# MCU.net
KiCad netlist of a schematic drawn in Altium Designer
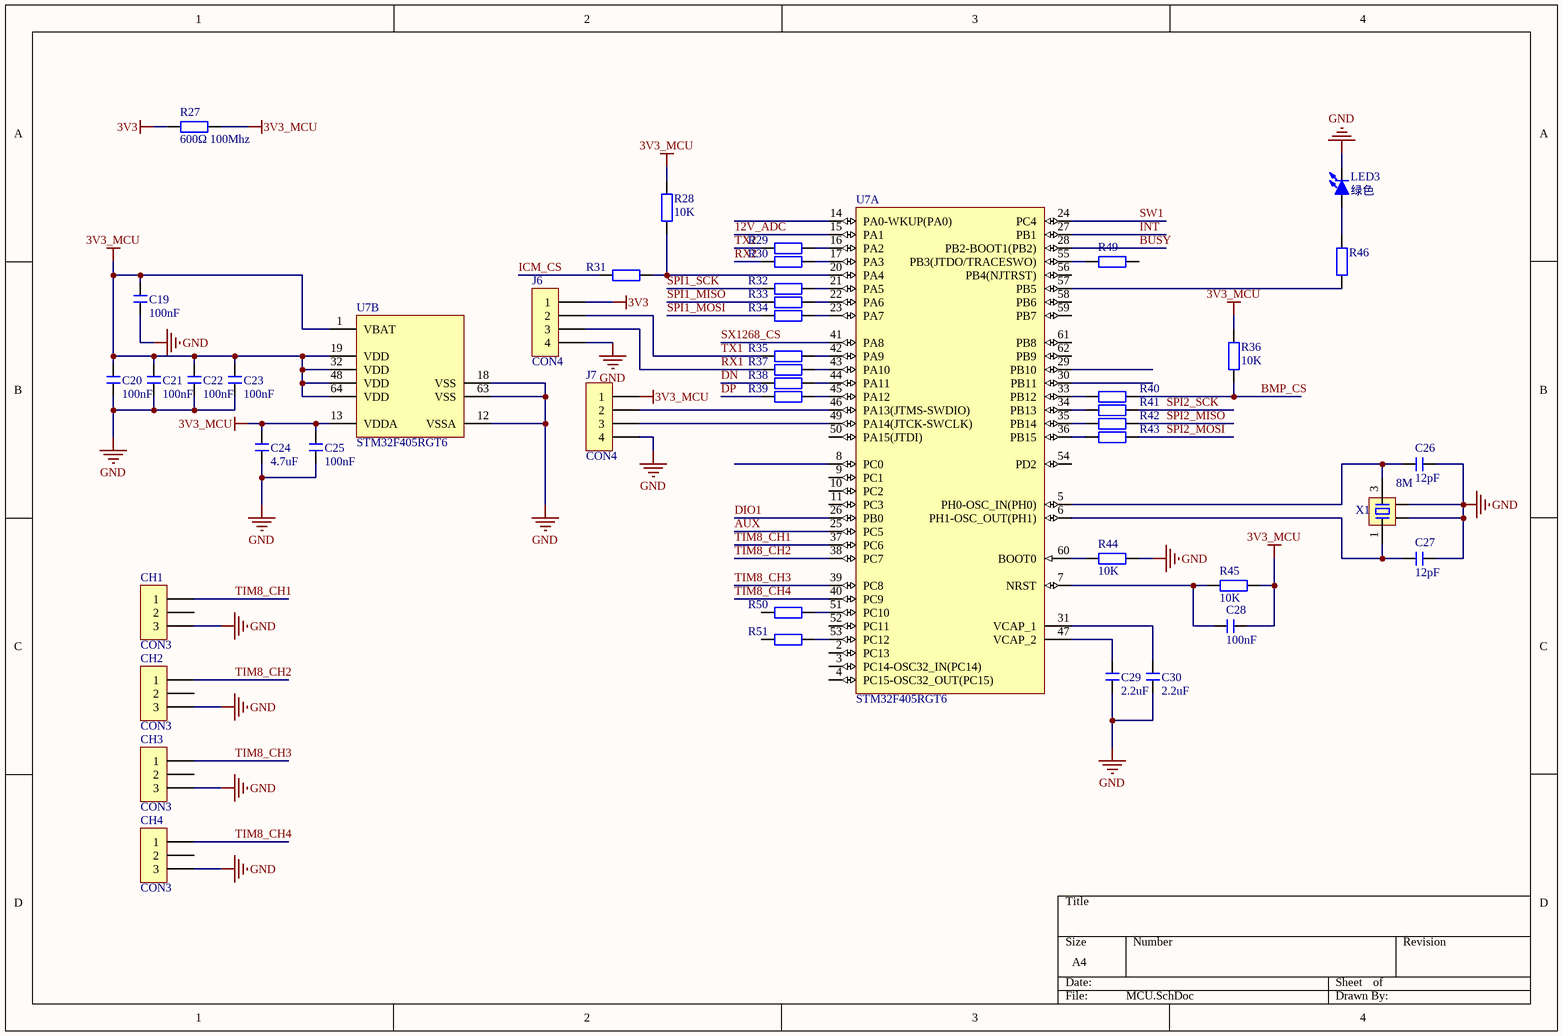
[diagram p0: MCU.SchDoc]

(export (version "E")
  (design (tool "Eeschema 10.0.6"))
  (components
    (comp (ref "C19")
      (value "100nF")
      (footprint "C 0603_L")
      (description "无极性贴片电容")
      (fields (field (name "版权归属") "源创客"))
      (libsource (lib "3.1   - 电阻-电容-电感") (part "C"))
    )
    (comp (ref "C20")
      (value "100nF")
      (footprint "C 0603_L")
      (description "无极性贴片电容")
      (fields (field (name "版权归属") "源创客"))
      (libsource (lib "3.1   - 电阻-电容-电感") (part "C"))
    )
    (comp (ref "C21")
      (value "100nF")
      (footprint "C 0603_L")
      (description "无极性贴片电容")
      (fields (field (name "版权归属") "源创客"))
      (libsource (lib "3.1   - 电阻-电容-电感") (part "C"))
    )
    (comp (ref "C22")
      (value "100nF")
      (footprint "C 0603_L")
      (description "无极性贴片电容")
      (fields (field (name "版权归属") "源创客"))
      (libsource (lib "3.1   - 电阻-电容-电感") (part "C"))
    )
    (comp (ref "C23")
      (value "100nF")
      (footprint "C 0603_L")
      (description "无极性贴片电容")
      (fields (field (name "版权归属") "源创客"))
      (libsource (lib "3.1   - 电阻-电容-电感") (part "C"))
    )
    (comp (ref "C24")
      (value "4.7uF")
      (footprint "C 0603_L")
      (description "无极性贴片电容")
      (fields (field (name "版权归属") "源创客"))
      (libsource (lib "3.1   - 电阻-电容-电感") (part "C"))
    )
    (comp (ref "C25")
      (value "100nF")
      (footprint "C 0603_L")
      (description "无极性贴片电容")
      (fields (field (name "版权归属") "源创客"))
      (libsource (lib "3.1   - 电阻-电容-电感") (part "C"))
    )
    (comp (ref "C26")
      (value "12pF")
      (footprint "C 0603_L")
      (description "无极性贴片电容")
      (fields (field (name "版权归属") "源创客"))
      (libsource (lib "3.1   - 电阻-电容-电感") (part "C"))
    )
    (comp (ref "C27")
      (value "12pF")
      (footprint "C 0603_L")
      (description "无极性贴片电容")
      (fields (field (name "版权归属") "源创客"))
      (libsource (lib "3.1   - 电阻-电容-电感") (part "C"))
    )
    (comp (ref "C28")
      (value "100nF")
      (footprint "C 0603_L")
      (description "无极性贴片电容")
      (fields (field (name "版权归属") "源创客"))
      (libsource (lib "3.1   - 电阻-电容-电感") (part "C"))
    )
    (comp (ref "C29")
      (value "2.2uF")
      (footprint "C 0603_L")
      (description "无极性贴片电容")
      (fields (field (name "版权归属") "源创客"))
      (libsource (lib "3.1   - 电阻-电容-电感") (part "C"))
    )
    (comp (ref "C30")
      (value "2.2uF")
      (footprint "C 0603_L")
      (description "无极性贴片电容")
      (fields (field (name "版权归属") "源创客"))
      (libsource (lib "3.1   - 电阻-电容-电感") (part "C"))
    )
    (comp (ref "CH1")
      (value "CON3")
      (footprint "HDR2.54-LI-3P")
      (description "Connector")
      (libsource (lib "插件") (part "CON3"))
    )
    (comp (ref "CH2")
      (value "CON3")
      (footprint "HDR2.54-LI-3P")
      (description "Connector")
      (libsource (lib "插件") (part "CON3"))
    )
    (comp (ref "CH3")
      (value "CON3")
      (footprint "HDR2.54-LI-3P")
      (description "Connector")
      (libsource (lib "插件") (part "CON3"))
    )
    (comp (ref "CH4")
      (value "CON3")
      (footprint "HDR2.54-LI-3P")
      (description "Connector")
      (libsource (lib "插件") (part "CON3"))
    )
    (comp (ref "J6")
      (value "CON4")
      (footprint "HDR2.54-LI-4P")
      (description "Connector")
      (libsource (lib "插件") (part "CON4"))
    )
    (comp (ref "J7")
      (value "CON4")
      (footprint "HDR2.54-LI-4P")
      (description "Connector")
      (libsource (lib "插件") (part "CON4"))
    )
    (comp (ref "LED3")
      (value "绿色")
      (footprint "LED 0805G")
      (description "贴片LED")
      (fields (field (name "版权归属") "源创客"))
      (libsource (lib "9.1   - LED") (part "LED-SMD"))
    )
    (comp (ref "R27")
      (value "600Ω 100Mhz")
      (footprint "R 0805_L")
      (description "磁珠")
      (fields (field (name "版权归属") "源创客"))
      (libsource (lib "3.1   - 电阻-电容-电感") (part "R"))
    )
    (comp (ref "R28")
      (value "10K")
      (footprint "R 0603_L")
      (description "贴片电阻")
      (fields (field (name "版权归属") "源创客"))
      (libsource (lib "3.1   - 电阻-电容-电感") (part "R"))
    )
    (comp (ref "R29")
      (value "~")
      (footprint "R 0603_L")
      (description "贴片电阻")
      (fields (field (name "版权归属") "源创客"))
      (libsource (lib "3.1   - 电阻-电容-电感") (part "R"))
    )
    (comp (ref "R30")
      (value "~")
      (footprint "R 0603_L")
      (description "贴片电阻")
      (fields (field (name "版权归属") "源创客"))
      (libsource (lib "3.1   - 电阻-电容-电感") (part "R"))
    )
    (comp (ref "R31")
      (value "~")
      (footprint "R 0603_L")
      (description "贴片电阻")
      (fields (field (name "版权归属") "源创客"))
      (libsource (lib "3.1   - 电阻-电容-电感") (part "R"))
    )
    (comp (ref "R32")
      (value "~")
      (footprint "R 0603_L")
      (description "贴片电阻")
      (fields (field (name "版权归属") "源创客"))
      (libsource (lib "3.1   - 电阻-电容-电感") (part "R"))
    )
    (comp (ref "R33")
      (value "~")
      (footprint "R 0603_L")
      (description "贴片电阻")
      (fields (field (name "版权归属") "源创客"))
      (libsource (lib "3.1   - 电阻-电容-电感") (part "R"))
    )
    (comp (ref "R34")
      (value "~")
      (footprint "R 0603_L")
      (description "贴片电阻")
      (fields (field (name "版权归属") "源创客"))
      (libsource (lib "3.1   - 电阻-电容-电感") (part "R"))
    )
    (comp (ref "R35")
      (value "~")
      (footprint "R 0603_L")
      (description "贴片电阻")
      (fields (field (name "版权归属") "源创客"))
      (libsource (lib "3.1   - 电阻-电容-电感") (part "R"))
    )
    (comp (ref "R36")
      (value "10K")
      (footprint "R 0603_L")
      (description "贴片电阻")
      (fields (field (name "版权归属") "源创客"))
      (libsource (lib "3.1   - 电阻-电容-电感") (part "R"))
    )
    (comp (ref "R37")
      (value "~")
      (footprint "R 0603_L")
      (description "贴片电阻")
      (fields (field (name "版权归属") "源创客"))
      (libsource (lib "3.1   - 电阻-电容-电感") (part "R"))
    )
    (comp (ref "R38")
      (value "~")
      (footprint "R 0603_L")
      (description "贴片电阻")
      (fields (field (name "版权归属") "源创客"))
      (libsource (lib "3.1   - 电阻-电容-电感") (part "R"))
    )
    (comp (ref "R39")
      (value "~")
      (footprint "R 0603_L")
      (description "贴片电阻")
      (fields (field (name "版权归属") "源创客"))
      (libsource (lib "3.1   - 电阻-电容-电感") (part "R"))
    )
    (comp (ref "R40")
      (value "~")
      (footprint "R 0603_L")
      (description "贴片电阻")
      (fields (field (name "版权归属") "源创客"))
      (libsource (lib "3.1   - 电阻-电容-电感") (part "R"))
    )
    (comp (ref "R41")
      (value "~")
      (footprint "R 0603_L")
      (description "贴片电阻")
      (fields (field (name "版权归属") "源创客"))
      (libsource (lib "3.1   - 电阻-电容-电感") (part "R"))
    )
    (comp (ref "R42")
      (value "~")
      (footprint "R 0603_L")
      (description "贴片电阻")
      (fields (field (name "版权归属") "源创客"))
      (libsource (lib "3.1   - 电阻-电容-电感") (part "R"))
    )
    (comp (ref "R43")
      (value "~")
      (footprint "R 0603_L")
      (description "贴片电阻")
      (fields (field (name "版权归属") "源创客"))
      (libsource (lib "3.1   - 电阻-电容-电感") (part "R"))
    )
    (comp (ref "R44")
      (value "10K")
      (footprint "R 0603_L")
      (description "贴片电阻")
      (fields (field (name "版权归属") "源创客"))
      (libsource (lib "3.1   - 电阻-电容-电感") (part "R"))
    )
    (comp (ref "R45")
      (value "10K")
      (footprint "R 0603_L")
      (description "贴片电阻")
      (fields (field (name "版权归属") "源创客"))
      (libsource (lib "3.1   - 电阻-电容-电感") (part "R"))
    )
    (comp (ref "R46")
      (value "~")
      (footprint "R 0603_L")
      (description "贴片电阻")
      (fields (field (name "版权归属") "源创客"))
      (libsource (lib "3.1   - 电阻-电容-电感") (part "R"))
    )
    (comp (ref "R49")
      (value "~")
      (footprint "R 0603_L")
      (description "贴片电阻")
      (fields (field (name "版权归属") "源创客"))
      (libsource (lib "3.1   - 电阻-电容-电感") (part "R"))
    )
    (comp (ref "R50")
      (value "~")
      (footprint "R 0603_L")
      (description "贴片电阻")
      (fields (field (name "版权归属") "源创客"))
      (libsource (lib "3.1   - 电阻-电容-电感") (part "R"))
    )
    (comp (ref "R51")
      (value "~")
      (footprint "R 0603_L")
      (description "贴片电阻")
      (fields (field (name "版权归属") "源创客"))
      (libsource (lib "3.1   - 电阻-电容-电感") (part "R"))
    )
    (comp (ref "U7")
      (value "STM32F405RGT6")
      (footprint "STM-LQFP64_N")
      (fields (field (name "MANUFACTURER") "STMicroelectronics"))
      (libsource (lib "") (part "STM32F405RGT6_1"))
    )
    (comp (ref "X1")
      (value "8M")
      (footprint "OSC 3225-4P")
      (fields (field (name "版权归属") "源创客"))
      (libsource (lib "10.1 - 保险丝-晶振") (part "XTAL-4P"))
    )
  )
  (nets
    (net (code "1") (name "/12V_ADC") (class "Default")
      (node (ref "U7") (pin "15") (pinfunction "PA1_15") (pintype "bidirectional"))
    )
    (net (code "2") (name "/AUX") (class "Default")
      (node (ref "U7") (pin "25") (pinfunction "PC5_25") (pintype "bidirectional"))
    )
    (net (code "3") (name "/BMP_CS") (class "Default")
      (node (ref "R36") (pin "1") (pinfunction "1_1") (pintype "passive"))
      (node (ref "R40") (pin "2") (pinfunction "2_2") (pintype "passive"))
    )
    (net (code "4") (name "/BUSY") (class "Default")
      (node (ref "U7") (pin "28") (pinfunction "PB2-BOOT1(PB2)_28") (pintype "bidirectional"))
    )
    (net (code "5") (name "/DIO1") (class "Default")
      (node (ref "U7") (pin "26") (pinfunction "PB0_26") (pintype "bidirectional"))
    )
    (net (code "6") (name "/DN") (class "Default")
      (node (ref "R38") (pin "2") (pinfunction "2_2") (pintype "passive"))
    )
    (net (code "7") (name "/DP") (class "Default")
      (node (ref "R39") (pin "2") (pinfunction "2_2") (pintype "passive"))
    )
    (net (code "8") (name "/ICM_CS") (class "Default")
      (node (ref "R31") (pin "2") (pinfunction "2_2") (pintype "passive"))
    )
    (net (code "9") (name "/INT") (class "Default")
      (node (ref "U7") (pin "27") (pinfunction "PB1_27") (pintype "bidirectional"))
    )
    (net (code "10") (name "/RX1") (class "Default")
      (node (ref "J6") (pin "3") (pinfunction "3_3") (pintype "passive"))
      (node (ref "R37") (pin "2") (pinfunction "2_2") (pintype "passive"))
    )
    (net (code "11") (name "/RX2") (class "Default")
      (node (ref "R30") (pin "2") (pinfunction "2_2") (pintype "passive"))
    )
    (net (code "12") (name "/SPI1_MISO") (class "Default")
      (node (ref "R33") (pin "2") (pinfunction "2_2") (pintype "passive"))
    )
    (net (code "13") (name "/SPI1_MOSI") (class "Default")
      (node (ref "R34") (pin "2") (pinfunction "2_2") (pintype "passive"))
    )
    (net (code "14") (name "/SPI1_SCK") (class "Default")
      (node (ref "R32") (pin "2") (pinfunction "2_2") (pintype "passive"))
    )
    (net (code "15") (name "/SPI2_MISO") (class "Default")
      (node (ref "R42") (pin "2") (pinfunction "2_2") (pintype "passive"))
    )
    (net (code "16") (name "/SPI2_MOSI") (class "Default")
      (node (ref "R43") (pin "2") (pinfunction "2_2") (pintype "passive"))
    )
    (net (code "17") (name "/SPI2_SCK") (class "Default")
      (node (ref "R41") (pin "2") (pinfunction "2_2") (pintype "passive"))
    )
    (net (code "18") (name "/SW1") (class "Default")
      (node (ref "U7") (pin "24") (pinfunction "PC4_24") (pintype "bidirectional"))
    )
    (net (code "19") (name "/SX1268_CS") (class "Default")
      (node (ref "U7") (pin "41") (pinfunction "PA8_41") (pintype "bidirectional"))
    )
    (net (code "20") (name "/TIM8_CH1") (class "Default")
      (node (ref "CH1") (pin "1") (pinfunction "1_1") (pintype "passive"))
      (node (ref "U7") (pin "37") (pinfunction "PC6_37") (pintype "bidirectional"))
    )
    (net (code "21") (name "/TIM8_CH2") (class "Default")
      (node (ref "CH2") (pin "1") (pinfunction "1_1") (pintype "passive"))
      (node (ref "U7") (pin "38") (pinfunction "PC7_38") (pintype "bidirectional"))
    )
    (net (code "22") (name "/TIM8_CH3") (class "Default")
      (node (ref "CH3") (pin "1") (pinfunction "1_1") (pintype "passive"))
      (node (ref "U7") (pin "39") (pinfunction "PC8_39") (pintype "bidirectional"))
    )
    (net (code "23") (name "/TIM8_CH4") (class "Default")
      (node (ref "CH4") (pin "1") (pinfunction "1_1") (pintype "passive"))
      (node (ref "U7") (pin "40") (pinfunction "PC9_40") (pintype "bidirectional"))
    )
    (net (code "24") (name "/TX1") (class "Default")
      (node (ref "J6") (pin "2") (pinfunction "2_2") (pintype "passive"))
      (node (ref "R35") (pin "2") (pinfunction "2_2") (pintype "passive"))
    )
    (net (code "25") (name "/TX2") (class "Default")
      (node (ref "R29") (pin "2") (pinfunction "2_2") (pintype "passive"))
    )
    (net (code "26") (name "3V3") (class "Default")
      (node (ref "J6") (pin "1") (pinfunction "1_1") (pintype "passive"))
      (node (ref "R27") (pin "1") (pinfunction "1_1") (pintype "passive"))
    )
    (net (code "27") (name "3V3_MCU") (class "Default")
      (node (ref "C19") (pin "2") (pinfunction "2_2") (pintype "passive"))
      (node (ref "C20") (pin "2") (pinfunction "2_2") (pintype "passive"))
      (node (ref "C21") (pin "2") (pinfunction "2_2") (pintype "passive"))
      (node (ref "C22") (pin "2") (pinfunction "2_2") (pintype "passive"))
      (node (ref "C23") (pin "2") (pinfunction "2_2") (pintype "passive"))
      (node (ref "C24") (pin "2") (pinfunction "2_2") (pintype "passive"))
      (node (ref "C25") (pin "2") (pinfunction "2_2") (pintype "passive"))
      (node (ref "C28") (pin "1") (pinfunction "1_1") (pintype "passive"))
      (node (ref "J7") (pin "1") (pinfunction "1_1") (pintype "passive"))
      (node (ref "R27") (pin "2") (pinfunction "2_2") (pintype "passive"))
      (node (ref "R28") (pin "2") (pinfunction "2_2") (pintype "passive"))
      (node (ref "R36") (pin "2") (pinfunction "2_2") (pintype "passive"))
      (node (ref "R45") (pin "2") (pinfunction "2_2") (pintype "passive"))
      (node (ref "U7") (pin "1") (pinfunction "VBAT_1") (pintype "power_in"))
      (node (ref "U7") (pin "13") (pinfunction "VDDA_13") (pintype "power_in"))
      (node (ref "U7") (pin "19") (pinfunction "VDD_19") (pintype "power_in"))
      (node (ref "U7") (pin "32") (pinfunction "VDD_32") (pintype "power_in"))
      (node (ref "U7") (pin "48") (pinfunction "VDD_48") (pintype "power_in"))
      (node (ref "U7") (pin "64") (pinfunction "VDD_64") (pintype "power_in"))
    )
    (net (code "28") (name "GND") (class "Default")
      (node (ref "C19") (pin "1") (pinfunction "1_1") (pintype "passive"))
      (node (ref "C20") (pin "1") (pinfunction "1_1") (pintype "passive"))
      (node (ref "C21") (pin "1") (pinfunction "1_1") (pintype "passive"))
      (node (ref "C22") (pin "1") (pinfunction "1_1") (pintype "passive"))
      (node (ref "C23") (pin "1") (pinfunction "1_1") (pintype "passive"))
      (node (ref "C24") (pin "1") (pinfunction "1_1") (pintype "passive"))
      (node (ref "C25") (pin "1") (pinfunction "1_1") (pintype "passive"))
      (node (ref "C26") (pin "1") (pinfunction "1_1") (pintype "passive"))
      (node (ref "C27") (pin "1") (pinfunction "1_1") (pintype "passive"))
      (node (ref "C29") (pin "1") (pinfunction "1_1") (pintype "passive"))
      (node (ref "C30") (pin "1") (pinfunction "1_1") (pintype "passive"))
      (node (ref "CH1") (pin "3") (pinfunction "3_3") (pintype "passive"))
      (node (ref "CH2") (pin "3") (pinfunction "3_3") (pintype "passive"))
      (node (ref "CH3") (pin "3") (pinfunction "3_3") (pintype "passive"))
      (node (ref "CH4") (pin "3") (pinfunction "3_3") (pintype "passive"))
      (node (ref "J6") (pin "4") (pinfunction "4_4") (pintype "passive"))
      (node (ref "J7") (pin "4") (pinfunction "4_4") (pintype "passive"))
      (node (ref "LED3") (pin "2") (pinfunction "K_2") (pintype "passive"))
      (node (ref "R44") (pin "2") (pinfunction "2_2") (pintype "passive"))
      (node (ref "U7") (pin "12") (pinfunction "VSSA_12") (pintype "power_in"))
      (node (ref "U7") (pin "18") (pinfunction "VSS_18") (pintype "power_in"))
      (node (ref "U7") (pin "63") (pinfunction "VSS_63") (pintype "power_in"))
      (node (ref "X1") (pin "2") (pinfunction "2_2") (pintype "passive"))
      (node (ref "X1") (pin "4") (pinfunction "4_4") (pintype "passive"))
    )
    (net (code "29") (name "Net-(LED3-A)") (class "Default")
      (node (ref "LED3") (pin "1") (pinfunction "A_1") (pintype "passive"))
      (node (ref "R46") (pin "2") (pinfunction "2_2") (pintype "passive"))
    )
    (net (code "30") (name "Net-(U7A-BOOT0)") (class "Default")
      (node (ref "R44") (pin "1") (pinfunction "1_1") (pintype "passive"))
      (node (ref "U7") (pin "60") (pinfunction "BOOT0_60") (pintype "input"))
    )
    (net (code "31") (name "Net-(U7A-NRST)") (class "Default")
      (node (ref "C28") (pin "2") (pinfunction "2_2") (pintype "passive"))
      (node (ref "R45") (pin "1") (pinfunction "1_1") (pintype "passive"))
      (node (ref "U7") (pin "7") (pinfunction "NRST_7") (pintype "bidirectional"))
    )
    (net (code "32") (name "Net-(U7A-PA2)") (class "Default")
      (node (ref "R29") (pin "1") (pinfunction "1_1") (pintype "passive"))
      (node (ref "U7") (pin "16") (pinfunction "PA2_16") (pintype "bidirectional"))
    )
    (net (code "33") (name "Net-(U7A-PA3)") (class "Default")
      (node (ref "R30") (pin "1") (pinfunction "1_1") (pintype "passive"))
      (node (ref "U7") (pin "17") (pinfunction "PA3_17") (pintype "bidirectional"))
    )
    (net (code "34") (name "Net-(U7A-PA4)") (class "Default")
      (node (ref "R28") (pin "1") (pinfunction "1_1") (pintype "passive"))
      (node (ref "R31") (pin "1") (pinfunction "1_1") (pintype "passive"))
      (node (ref "U7") (pin "20") (pinfunction "PA4_20") (pintype "bidirectional"))
    )
    (net (code "35") (name "Net-(U7A-PA5)") (class "Default")
      (node (ref "R32") (pin "1") (pinfunction "1_1") (pintype "passive"))
      (node (ref "U7") (pin "21") (pinfunction "PA5_21") (pintype "bidirectional"))
    )
    (net (code "36") (name "Net-(U7A-PA6)") (class "Default")
      (node (ref "R33") (pin "1") (pinfunction "1_1") (pintype "passive"))
      (node (ref "U7") (pin "22") (pinfunction "PA6_22") (pintype "bidirectional"))
    )
    (net (code "37") (name "Net-(U7A-PA7)") (class "Default")
      (node (ref "R34") (pin "1") (pinfunction "1_1") (pintype "passive"))
      (node (ref "U7") (pin "23") (pinfunction "PA7_23") (pintype "bidirectional"))
    )
    (net (code "38") (name "Net-(U7A-PA9)") (class "Default")
      (node (ref "R35") (pin "1") (pinfunction "1_1") (pintype "passive"))
      (node (ref "U7") (pin "42") (pinfunction "PA9_42") (pintype "bidirectional"))
    )
    (net (code "39") (name "Net-(U7A-PA10)") (class "Default")
      (node (ref "R37") (pin "1") (pinfunction "1_1") (pintype "passive"))
      (node (ref "U7") (pin "43") (pinfunction "PA10_43") (pintype "bidirectional"))
    )
    (net (code "40") (name "Net-(U7A-PA11)") (class "Default")
      (node (ref "R38") (pin "1") (pinfunction "1_1") (pintype "passive"))
      (node (ref "U7") (pin "44") (pinfunction "PA11_44") (pintype "bidirectional"))
    )
    (net (code "41") (name "Net-(U7A-PA12)") (class "Default")
      (node (ref "R39") (pin "1") (pinfunction "1_1") (pintype "passive"))
      (node (ref "U7") (pin "45") (pinfunction "PA12_45") (pintype "bidirectional"))
    )
    (net (code "42") (name "Net-(U7A-PA13(JTMS-SWDIO))") (class "Default")
      (node (ref "J7") (pin "2") (pinfunction "2_2") (pintype "passive"))
      (node (ref "U7") (pin "46") (pinfunction "PA13(JTMS-SWDIO)_46") (pintype "bidirectional"))
    )
    (net (code "43") (name "Net-(U7A-PA14(JTCK-SWCLK))") (class "Default")
      (node (ref "J7") (pin "3") (pinfunction "3_3") (pintype "passive"))
      (node (ref "U7") (pin "49") (pinfunction "PA14(JTCK-SWCLK)_49") (pintype "bidirectional"))
    )
    (net (code "44") (name "Net-(U7A-PB3(JTDO{slash}TRACESWO))") (class "Default")
      (node (ref "R49") (pin "1") (pinfunction "1_1") (pintype "passive"))
      (node (ref "U7") (pin "55") (pinfunction "PB3(JTDO/TRACESWO)_55") (pintype "bidirectional"))
    )
    (net (code "45") (name "Net-(U7A-PB5)") (class "Default")
      (node (ref "R46") (pin "1") (pinfunction "1_1") (pintype "passive"))
      (node (ref "U7") (pin "57") (pinfunction "PB5_57") (pintype "bidirectional"))
    )
    (net (code "46") (name "Net-(U7A-PB12)") (class "Default")
      (node (ref "R40") (pin "1") (pinfunction "1_1") (pintype "passive"))
      (node (ref "U7") (pin "33") (pinfunction "PB12_33") (pintype "bidirectional"))
    )
    (net (code "47") (name "Net-(U7A-PB13)") (class "Default")
      (node (ref "R41") (pin "1") (pinfunction "1_1") (pintype "passive"))
      (node (ref "U7") (pin "34") (pinfunction "PB13_34") (pintype "bidirectional"))
    )
    (net (code "48") (name "Net-(U7A-PB14)") (class "Default")
      (node (ref "R42") (pin "1") (pinfunction "1_1") (pintype "passive"))
      (node (ref "U7") (pin "35") (pinfunction "PB14_35") (pintype "bidirectional"))
    )
    (net (code "49") (name "Net-(U7A-PB15)") (class "Default")
      (node (ref "R43") (pin "1") (pinfunction "1_1") (pintype "passive"))
      (node (ref "U7") (pin "36") (pinfunction "PB15_36") (pintype "bidirectional"))
    )
    (net (code "50") (name "Net-(U7A-PC10)") (class "Default")
      (node (ref "R50") (pin "1") (pinfunction "1_1") (pintype "passive"))
      (node (ref "U7") (pin "51") (pinfunction "PC10_51") (pintype "bidirectional"))
    )
    (net (code "51") (name "Net-(U7A-PC12)") (class "Default")
      (node (ref "R51") (pin "1") (pinfunction "1_1") (pintype "passive"))
      (node (ref "U7") (pin "53") (pinfunction "PC12_53") (pintype "bidirectional"))
    )
    (net (code "52") (name "Net-(U7A-PH0-OSC_IN(PH0))") (class "Default")
      (node (ref "C26") (pin "2") (pinfunction "2_2") (pintype "passive"))
      (node (ref "U7") (pin "5") (pinfunction "PH0-OSC_IN(PH0)_5") (pintype "bidirectional"))
      (node (ref "X1") (pin "3") (pinfunction "3_3") (pintype "passive"))
    )
    (net (code "53") (name "Net-(U7A-PH1-OSC_OUT(PH1))") (class "Default")
      (node (ref "C27") (pin "2") (pinfunction "2_2") (pintype "passive"))
      (node (ref "U7") (pin "6") (pinfunction "PH1-OSC_OUT(PH1)_6") (pintype "bidirectional"))
      (node (ref "X1") (pin "1") (pinfunction "1_1") (pintype "passive"))
    )
    (net (code "54") (name "Net-(U7A-VCAP_1)") (class "Default")
      (node (ref "C30") (pin "2") (pinfunction "2_2") (pintype "passive"))
      (node (ref "U7") (pin "31") (pinfunction "VCAP_1_31") (pintype "power_in"))
    )
    (net (code "55") (name "Net-(U7A-VCAP_2)") (class "Default")
      (node (ref "C29") (pin "2") (pinfunction "2_2") (pintype "passive"))
      (node (ref "U7") (pin "47") (pinfunction "VCAP_2_47") (pintype "power_in"))
    )
    (net (code "56") (name "unconnected-(CH1-Pad2)") (class "Default")
      (node (ref "CH1") (pin "2") (pinfunction "2_2") (pintype "passive"))
    )
    (net (code "57") (name "unconnected-(CH2-Pad2)") (class "Default")
      (node (ref "CH2") (pin "2") (pinfunction "2_2") (pintype "passive"))
    )
    (net (code "58") (name "unconnected-(CH3-Pad2)") (class "Default")
      (node (ref "CH3") (pin "2") (pinfunction "2_2") (pintype "passive"))
    )
    (net (code "59") (name "unconnected-(CH4-Pad2)") (class "Default")
      (node (ref "CH4") (pin "2") (pinfunction "2_2") (pintype "passive"))
    )
    (net (code "60") (name "unconnected-(R49-Pad2)") (class "Default")
      (node (ref "R49") (pin "2") (pinfunction "2_2") (pintype "passive"))
    )
    (net (code "61") (name "unconnected-(R50-Pad2)") (class "Default")
      (node (ref "R50") (pin "2") (pinfunction "2_2") (pintype "passive"))
    )
    (net (code "62") (name "unconnected-(R51-Pad2)") (class "Default")
      (node (ref "R51") (pin "2") (pinfunction "2_2") (pintype "passive"))
    )
    (net (code "63") (name "unconnected-(U7A-PA0-WKUP(PA0)-Pad14)") (class "Default")
      (node (ref "U7") (pin "14") (pinfunction "PA0-WKUP(PA0)_14") (pintype "bidirectional"))
    )
    (net (code "64") (name "unconnected-(U7A-PA15(JTDI)-Pad50)") (class "Default")
      (node (ref "U7") (pin "50") (pinfunction "PA15(JTDI)_50") (pintype "bidirectional"))
    )
    (net (code "65") (name "unconnected-(U7A-PB4(NJTRST)-Pad56)") (class "Default")
      (node (ref "U7") (pin "56") (pinfunction "PB4(NJTRST)_56") (pintype "bidirectional"))
    )
    (net (code "66") (name "unconnected-(U7A-PB6-Pad58)") (class "Default")
      (node (ref "U7") (pin "58") (pinfunction "PB6_58") (pintype "bidirectional"))
    )
    (net (code "67") (name "unconnected-(U7A-PB7-Pad59)") (class "Default")
      (node (ref "U7") (pin "59") (pinfunction "PB7_59") (pintype "bidirectional"))
    )
    (net (code "68") (name "unconnected-(U7A-PB8-Pad61)") (class "Default")
      (node (ref "U7") (pin "61") (pinfunction "PB8_61") (pintype "bidirectional"))
    )
    (net (code "69") (name "unconnected-(U7A-PB9-Pad62)") (class "Default")
      (node (ref "U7") (pin "62") (pinfunction "PB9_62") (pintype "bidirectional"))
    )
    (net (code "70") (name "unconnected-(U7A-PB10-Pad29)") (class "Default")
      (node (ref "U7") (pin "29") (pinfunction "PB10_29") (pintype "bidirectional"))
    )
    (net (code "71") (name "unconnected-(U7A-PB11-Pad30)") (class "Default")
      (node (ref "U7") (pin "30") (pinfunction "PB11_30") (pintype "bidirectional"))
    )
    (net (code "72") (name "unconnected-(U7A-PC0-Pad8)") (class "Default")
      (node (ref "U7") (pin "8") (pinfunction "PC0_8") (pintype "bidirectional"))
    )
    (net (code "73") (name "unconnected-(U7A-PC1-Pad9)") (class "Default")
      (node (ref "U7") (pin "9") (pinfunction "PC1_9") (pintype "bidirectional"))
    )
    (net (code "74") (name "unconnected-(U7A-PC2-Pad10)") (class "Default")
      (node (ref "U7") (pin "10") (pinfunction "PC2_10") (pintype "bidirectional"))
    )
    (net (code "75") (name "unconnected-(U7A-PC3-Pad11)") (class "Default")
      (node (ref "U7") (pin "11") (pinfunction "PC3_11") (pintype "bidirectional"))
    )
    (net (code "76") (name "unconnected-(U7A-PC11-Pad52)") (class "Default")
      (node (ref "U7") (pin "52") (pinfunction "PC11_52") (pintype "bidirectional"))
    )
    (net (code "77") (name "unconnected-(U7A-PC13-Pad2)") (class "Default")
      (node (ref "U7") (pin "2") (pinfunction "PC13_2") (pintype "bidirectional"))
    )
    (net (code "78") (name "unconnected-(U7A-PC14-OSC32_IN(PC14)-Pad3)") (class "Default")
      (node (ref "U7") (pin "3") (pinfunction "PC14-OSC32_IN(PC14)_3") (pintype "bidirectional"))
    )
    (net (code "79") (name "unconnected-(U7A-PC15-OSC32_OUT(PC15)-Pad4)") (class "Default")
      (node (ref "U7") (pin "4") (pinfunction "PC15-OSC32_OUT(PC15)_4") (pintype "bidirectional"))
    )
    (net (code "80") (name "unconnected-(U7A-PD2-Pad54)") (class "Default")
      (node (ref "U7") (pin "54") (pinfunction "PD2_54") (pintype "bidirectional"))
    )
  )
)
